# IncubPower.net
KiCad netlist of a schematic drawn in EAGLE
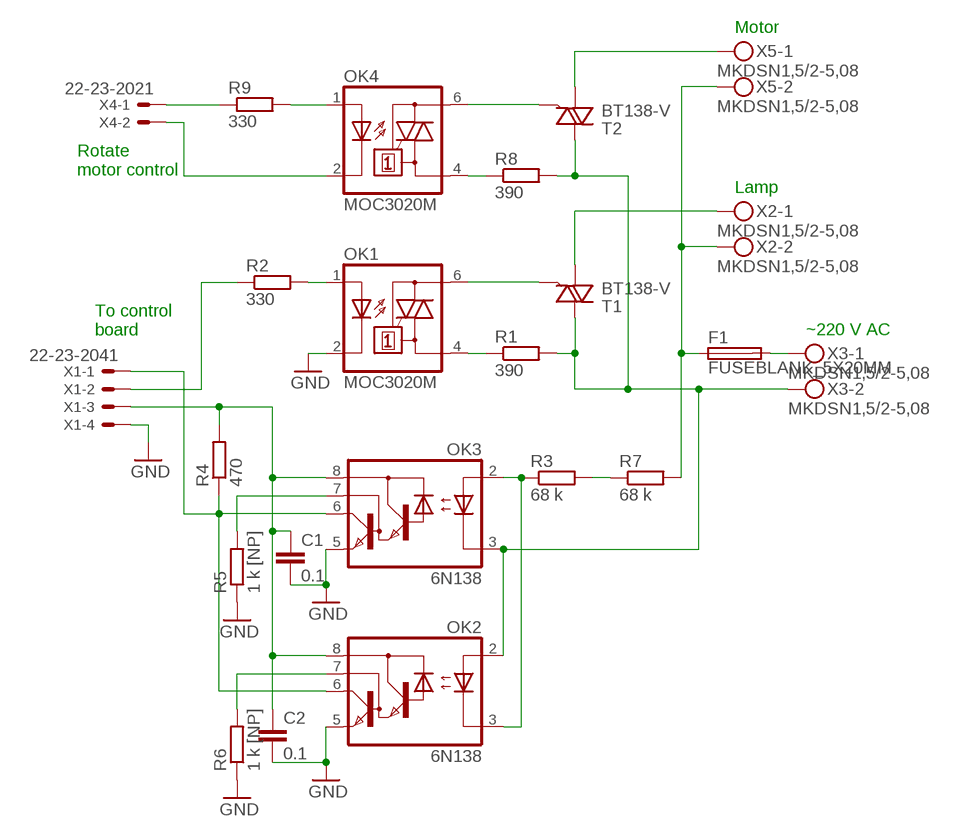
[diagram p0: schematic, sheet 1]

(export (version "E")
  (design (tool "Eeschema 10.0.6"))
  (components
    (comp (ref "C1")
      (value "0.1")
      (footprint "eagle-import:C0805")
      (libsource (lib "eagle-import") (part "C-EUC0805"))
    )
    (comp (ref "C2")
      (value "0.1")
      (footprint "eagle-import:C0805")
      (libsource (lib "eagle-import") (part "C-EUC0805"))
    )
    (comp (ref "F1")
      (value "FUSEBLANK_5X20MM")
      (footprint "eagle-import:FUSE_HOLDER_5X20MM")
      (libsource (lib "eagle-import") (part "FUSEBLANK_5X20MM"))
    )
    (comp (ref "OK1")
      (value "MOC3020M")
      (footprint "eagle-import:DIL06")
      (fields (field (name "MF") "FAIRCHILD SEMICONDUCTOR") (field (name "MPN") "MOC3020-M"))
      (libsource (lib "eagle-import") (part "MOC30M20"))
    )
    (comp (ref "OK2")
      (value "6N138")
      (footprint "eagle-import:DIL08")
      (fields (field (name "MF") "VISHAY/TELEFUNKEN"))
      (libsource (lib "eagle-import") (part "6N138"))
    )
    (comp (ref "OK3")
      (value "6N138")
      (footprint "eagle-import:DIL08")
      (fields (field (name "MF") "VISHAY/TELEFUNKEN"))
      (libsource (lib "eagle-import") (part "6N138"))
    )
    (comp (ref "OK4")
      (value "MOC3020M")
      (footprint "eagle-import:DIL06")
      (fields (field (name "MF") "FAIRCHILD SEMICONDUCTOR") (field (name "MPN") "MOC3020-M"))
      (libsource (lib "eagle-import") (part "MOC30M20"))
    )
    (comp (ref "R1")
      (value "390")
      (footprint "eagle-import:0204_7")
      (libsource (lib "eagle-import") (part "R-EU_0204/7"))
    )
    (comp (ref "R2")
      (value "330")
      (footprint "eagle-import:R0805")
      (libsource (lib "eagle-import") (part "R-EU_R0805"))
    )
    (comp (ref "R3")
      (value "68 k")
      (footprint "eagle-import:0204_7")
      (libsource (lib "eagle-import") (part "resistor_R-EU_0204/7"))
    )
    (comp (ref "R4")
      (value "470")
      (footprint "eagle-import:R0805")
      (libsource (lib "eagle-import") (part "R-EU_R0805"))
    )
    (comp (ref "R5")
      (value "1 k [NP]")
      (footprint "eagle-import:R0805")
      (libsource (lib "eagle-import") (part "R-EU_R0805"))
    )
    (comp (ref "R6")
      (value "1 k [NP]")
      (footprint "eagle-import:R0805")
      (libsource (lib "eagle-import") (part "R-EU_R0805"))
    )
    (comp (ref "R7")
      (value "68 k")
      (footprint "eagle-import:0204_7")
      (libsource (lib "eagle-import") (part "resistor_R-EU_0204/7"))
    )
    (comp (ref "R8")
      (value "390")
      (footprint "eagle-import:0204_7")
      (libsource (lib "eagle-import") (part "R-EU_0204/7"))
    )
    (comp (ref "R9")
      (value "330")
      (footprint "eagle-import:R0805")
      (libsource (lib "eagle-import") (part "R-EU_R0805"))
    )
    (comp (ref "T1")
      (value "BT138-V")
      (footprint "eagle-import:TO220BV")
      (libsource (lib "eagle-import") (part "BT138-V"))
    )
    (comp (ref "T2")
      (value "BT138-V")
      (footprint "eagle-import:TO220BV")
      (libsource (lib "eagle-import") (part "BT138-V"))
    )
    (comp (ref "X1")
      (value "22-23-2041")
      (footprint "eagle-import:22-23-2041")
      (fields (field (name "MF") "MOLEX"))
      (libsource (lib "eagle-import") (part "22-23-2041"))
    )
    (comp (ref "X2")
      (value "MKDSN1,5/2-5,08")
      (footprint "eagle-import:MKDSN1,5_2-5,08")
      (fields (field (name "MPN") "MKDSN 1,5/2-5.08"))
      (libsource (lib "eagle-import") (part "MKDSN1,5/2-5,08"))
    )
    (comp (ref "X3")
      (value "MKDSN1,5/2-5,08")
      (footprint "eagle-import:MKDSN1,5_2-5,08")
      (fields (field (name "MPN") "MKDSN 1,5/2-5.08"))
      (libsource (lib "eagle-import") (part "MKDSN1,5/2-5,08"))
    )
    (comp (ref "X4")
      (value "22-23-2021")
      (footprint "eagle-import:22-23-2021")
      (fields (field (name "MF") "MOLEX"))
      (libsource (lib "eagle-import") (part "22-23-2021"))
    )
    (comp (ref "X5")
      (value "MKDSN1,5/2-5,08")
      (footprint "eagle-import:MKDSN1,5_2-5,08")
      (fields (field (name "MPN") "MKDSN 1,5/2-5.08"))
      (libsource (lib "eagle-import") (part "MKDSN1,5/2-5,08"))
    )
  )
  (nets
    (net (code "1") (name "GND") (class "Default")
      (node (ref "C1") (pin "2") (pinfunction "2_2") (pintype "passive"))
      (node (ref "C2") (pin "2") (pinfunction "2_2") (pintype "passive"))
      (node (ref "OK1") (pin "2") (pinfunction "C_2") (pintype "passive"))
      (node (ref "OK2") (pin "5") (pinfunction "GND_5") (pintype "passive"))
      (node (ref "OK3") (pin "5") (pinfunction "GND_5") (pintype "passive"))
      (node (ref "R5") (pin "1") (pinfunction "1_1") (pintype "passive"))
      (node (ref "R6") (pin "1") (pinfunction "1_1") (pintype "passive"))
      (node (ref "X1") (pin "4") (pinfunction "S_4") (pintype "passive"))
    )
    (net (code "2") (name "Net-(OK1-A)") (class "Default")
      (node (ref "OK1") (pin "1") (pinfunction "A_1") (pintype "passive"))
      (node (ref "R2") (pin "2") (pinfunction "2_2") (pintype "passive"))
    )
    (net (code "3") (name "Net-(OK1-A1)") (class "Default")
      (node (ref "OK1") (pin "4") (pinfunction "A1_4") (pintype "passive"))
      (node (ref "R1") (pin "1") (pinfunction "1_1") (pintype "passive"))
    )
    (net (code "4") (name "Net-(OK1-A2)") (class "Default")
      (node (ref "OK1") (pin "6") (pinfunction "A2_6") (pintype "passive"))
      (node (ref "T1") (pin "G") (pinfunction "G_G") (pintype "passive"))
    )
    (net (code "5") (name "Net-(OK2-A)") (class "Default")
      (node (ref "OK2") (pin "2") (pinfunction "A_2") (pintype "passive"))
      (node (ref "OK3") (pin "3") (pinfunction "C_3") (pintype "passive"))
      (node (ref "R1") (pin "2") (pinfunction "2_2") (pintype "passive"))
      (node (ref "R8") (pin "2") (pinfunction "2_2") (pintype "passive"))
      (node (ref "T1") (pin "T2") (pinfunction "A2_T2") (pintype "passive"))
      (node (ref "T2") (pin "T2") (pinfunction "A2_T2") (pintype "passive"))
      (node (ref "X3") (pin "2") (pinfunction "KL_2") (pintype "passive"))
    )
    (net (code "6") (name "Net-(OK2-C)") (class "Default")
      (node (ref "OK2") (pin "3") (pinfunction "C_3") (pintype "passive"))
      (node (ref "OK3") (pin "2") (pinfunction "A_2") (pintype "passive"))
      (node (ref "R3") (pin "1") (pinfunction "1_1") (pintype "passive"))
    )
    (net (code "7") (name "Net-(OK2-VB)") (class "Default")
      (node (ref "OK2") (pin "7") (pinfunction "VB_7") (pintype "passive"))
      (node (ref "R6") (pin "2") (pinfunction "2_2") (pintype "passive"))
    )
    (net (code "8") (name "Net-(OK2-VCC)") (class "Default")
      (node (ref "C1") (pin "1") (pinfunction "1_1") (pintype "passive"))
      (node (ref "C2") (pin "1") (pinfunction "1_1") (pintype "passive"))
      (node (ref "OK2") (pin "8") (pinfunction "VCC_8") (pintype "passive"))
      (node (ref "OK3") (pin "8") (pinfunction "VCC_8") (pintype "passive"))
      (node (ref "R4") (pin "2") (pinfunction "2_2") (pintype "passive"))
      (node (ref "X1") (pin "3") (pinfunction "S_3") (pintype "passive"))
    )
    (net (code "9") (name "Net-(OK2-VO)") (class "Default")
      (node (ref "OK2") (pin "6") (pinfunction "VO_6") (pintype "passive"))
      (node (ref "OK3") (pin "6") (pinfunction "VO_6") (pintype "passive"))
      (node (ref "R4") (pin "1") (pinfunction "1_1") (pintype "passive"))
      (node (ref "X1") (pin "1") (pinfunction "S_1") (pintype "passive"))
    )
    (net (code "10") (name "Net-(OK3-VB)") (class "Default")
      (node (ref "OK3") (pin "7") (pinfunction "VB_7") (pintype "passive"))
      (node (ref "R5") (pin "2") (pinfunction "2_2") (pintype "passive"))
    )
    (net (code "11") (name "Net-(OK4-A)") (class "Default")
      (node (ref "OK4") (pin "1") (pinfunction "A_1") (pintype "passive"))
      (node (ref "R9") (pin "2") (pinfunction "2_2") (pintype "passive"))
    )
    (net (code "12") (name "Net-(OK4-A1)") (class "Default")
      (node (ref "OK4") (pin "4") (pinfunction "A1_4") (pintype "passive"))
      (node (ref "R8") (pin "1") (pinfunction "1_1") (pintype "passive"))
    )
    (net (code "13") (name "Net-(OK4-A2)") (class "Default")
      (node (ref "OK4") (pin "6") (pinfunction "A2_6") (pintype "passive"))
      (node (ref "T2") (pin "G") (pinfunction "G_G") (pintype "passive"))
    )
    (net (code "14") (name "Net-(OK4-C)") (class "Default")
      (node (ref "OK4") (pin "2") (pinfunction "C_2") (pintype "passive"))
      (node (ref "X4") (pin "2") (pinfunction "S_2") (pintype "passive"))
    )
    (net (code "15") (name "Net-(R3-Pad2)") (class "Default")
      (node (ref "R3") (pin "2") (pinfunction "2_2") (pintype "passive"))
      (node (ref "R7") (pin "1") (pinfunction "1_1") (pintype "passive"))
    )
    (net (code "16") (name "Net-(T1-A1)") (class "Default")
      (node (ref "T1") (pin "T1") (pinfunction "A1_T1") (pintype "passive"))
      (node (ref "X2") (pin "1") (pinfunction "KL_1") (pintype "passive"))
    )
    (net (code "17") (name "Net-(T2-A1)") (class "Default")
      (node (ref "T2") (pin "T1") (pinfunction "A1_T1") (pintype "passive"))
      (node (ref "X5") (pin "1") (pinfunction "KL_1") (pintype "passive"))
    )
    (net (code "18") (name "Net-(X1B-S)") (class "Default")
      (node (ref "R2") (pin "1") (pinfunction "1_1") (pintype "passive"))
      (node (ref "X1") (pin "2") (pinfunction "S_2") (pintype "passive"))
    )
    (net (code "19") (name "Net-(X2B-KL)") (class "Default")
      (node (ref "F1") (pin "1") (pinfunction "1_1") (pintype "passive"))
      (node (ref "R7") (pin "2") (pinfunction "2_2") (pintype "passive"))
      (node (ref "X2") (pin "2") (pinfunction "KL_2") (pintype "passive"))
      (node (ref "X5") (pin "2") (pinfunction "KL_2") (pintype "passive"))
    )
    (net (code "20") (name "Net-(X3A-KL)") (class "Default")
      (node (ref "F1") (pin "2") (pinfunction "2_2") (pintype "passive"))
      (node (ref "X3") (pin "1") (pinfunction "KL_1") (pintype "passive"))
    )
    (net (code "21") (name "Net-(X4A-S)") (class "Default")
      (node (ref "R9") (pin "1") (pinfunction "1_1") (pintype "passive"))
      (node (ref "X4") (pin "1") (pinfunction "S_1") (pintype "passive"))
    )
  )
)
